# TP4056mCH.net
KiCad netlist of a schematic drawn in EAGLE
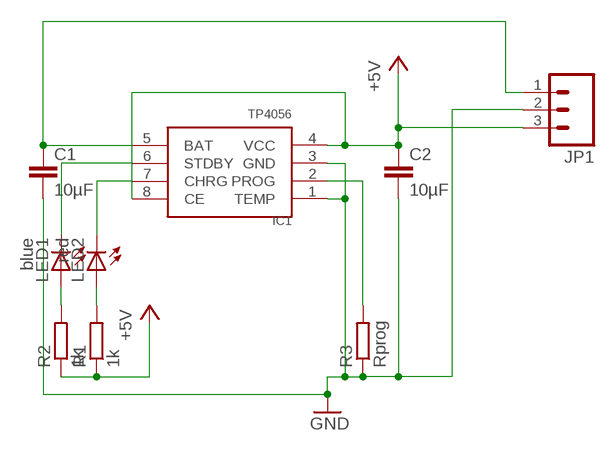
[diagram p0: schematic, sheet 1]

(export (version "E")
  (design (tool "Eeschema 10.0.6"))
  (components
    (comp (ref "C1")
      (value "10µF")
      (footprint "eagle-import:C0805")
      (libsource (lib "eagle-import") (part "C-EUC0805"))
    )
    (comp (ref "C2")
      (value "10µF")
      (footprint "eagle-import:C0805")
      (libsource (lib "eagle-import") (part "C-EUC0805"))
    )
    (comp (ref "IC1")
      (value "TP4056")
      (footprint "eagle-import:SOP-8")
      (libsource (lib "eagle-import") (part "TP4056"))
    )
    (comp (ref "JP1")
      (value "M03PTH")
      (footprint "eagle-import:1X03")
      (libsource (lib "eagle-import") (part "M03PTH"))
    )
    (comp (ref "LED1")
      (value "blue")
      (footprint "eagle-import:CHIP-LED0805")
      (libsource (lib "eagle-import") (part "LEDCHIP-LED0805"))
    )
    (comp (ref "LED2")
      (value "red")
      (footprint "eagle-import:CHIP-LED0805")
      (libsource (lib "eagle-import") (part "LEDCHIP-LED0805"))
    )
    (comp (ref "R1")
      (value "1k")
      (footprint "eagle-import:R0603")
      (libsource (lib "eagle-import") (part "R-EU_R0603"))
    )
    (comp (ref "R2")
      (value "1k")
      (footprint "eagle-import:R0603")
      (libsource (lib "eagle-import") (part "R-EU_R0603"))
    )
    (comp (ref "R3")
      (value "Rprog")
      (footprint "eagle-import:R0603")
      (libsource (lib "eagle-import") (part "R-EU_R0603"))
    )
  )
  (nets
    (net (code "1") (name "+5V") (class "Default")
      (node (ref "C2") (pin "1") (pinfunction "1_1") (pintype "passive"))
      (node (ref "IC1") (pin "4") (pinfunction "VCC_4") (pintype "bidirectional"))
      (node (ref "IC1") (pin "8") (pinfunction "CE_8") (pintype "bidirectional"))
      (node (ref "JP1") (pin "3") (pinfunction "3_3") (pintype "passive"))
      (node (ref "R1") (pin "1") (pinfunction "1_1") (pintype "passive"))
      (node (ref "R2") (pin "1") (pinfunction "1_1") (pintype "passive"))
    )
    (net (code "2") (name "GND") (class "Default")
      (node (ref "C1") (pin "2") (pinfunction "2_2") (pintype "passive"))
      (node (ref "C2") (pin "2") (pinfunction "2_2") (pintype "passive"))
      (node (ref "IC1") (pin "1") (pinfunction "TEMP_1") (pintype "bidirectional"))
      (node (ref "IC1") (pin "3") (pinfunction "GND_3") (pintype "bidirectional"))
      (node (ref "JP1") (pin "2") (pinfunction "2_2") (pintype "passive"))
      (node (ref "R3") (pin "1") (pinfunction "1_1") (pintype "passive"))
    )
    (net (code "3") (name "Net-(IC1-BAT)") (class "Default")
      (node (ref "C1") (pin "1") (pinfunction "1_1") (pintype "passive"))
      (node (ref "IC1") (pin "5") (pinfunction "BAT_5") (pintype "bidirectional"))
      (node (ref "JP1") (pin "1") (pinfunction "1_1") (pintype "passive"))
    )
    (net (code "4") (name "Net-(IC1-CHRG)") (class "Default")
      (node (ref "IC1") (pin "7") (pinfunction "CHRG_7") (pintype "bidirectional"))
      (node (ref "LED2") (pin "C") (pinfunction "C_C") (pintype "passive"))
    )
    (net (code "5") (name "Net-(IC1-PROG)") (class "Default")
      (node (ref "IC1") (pin "2") (pinfunction "PROG_2") (pintype "bidirectional"))
      (node (ref "R3") (pin "2") (pinfunction "2_2") (pintype "passive"))
    )
    (net (code "6") (name "Net-(IC1-STDBY)") (class "Default")
      (node (ref "IC1") (pin "6") (pinfunction "STDBY_6") (pintype "bidirectional"))
      (node (ref "LED1") (pin "C") (pinfunction "C_C") (pintype "passive"))
    )
    (net (code "7") (name "Net-(LED1-PadA)") (class "Default")
      (node (ref "LED1") (pin "A") (pinfunction "A_A") (pintype "passive"))
      (node (ref "R2") (pin "2") (pinfunction "2_2") (pintype "passive"))
    )
    (net (code "8") (name "Net-(LED2-PadA)") (class "Default")
      (node (ref "LED2") (pin "A") (pinfunction "A_A") (pintype "passive"))
      (node (ref "R1") (pin "2") (pinfunction "2_2") (pintype "passive"))
    )
  )
)
